# rev2.net
KiCad netlist of a schematic drawn in EAGLE
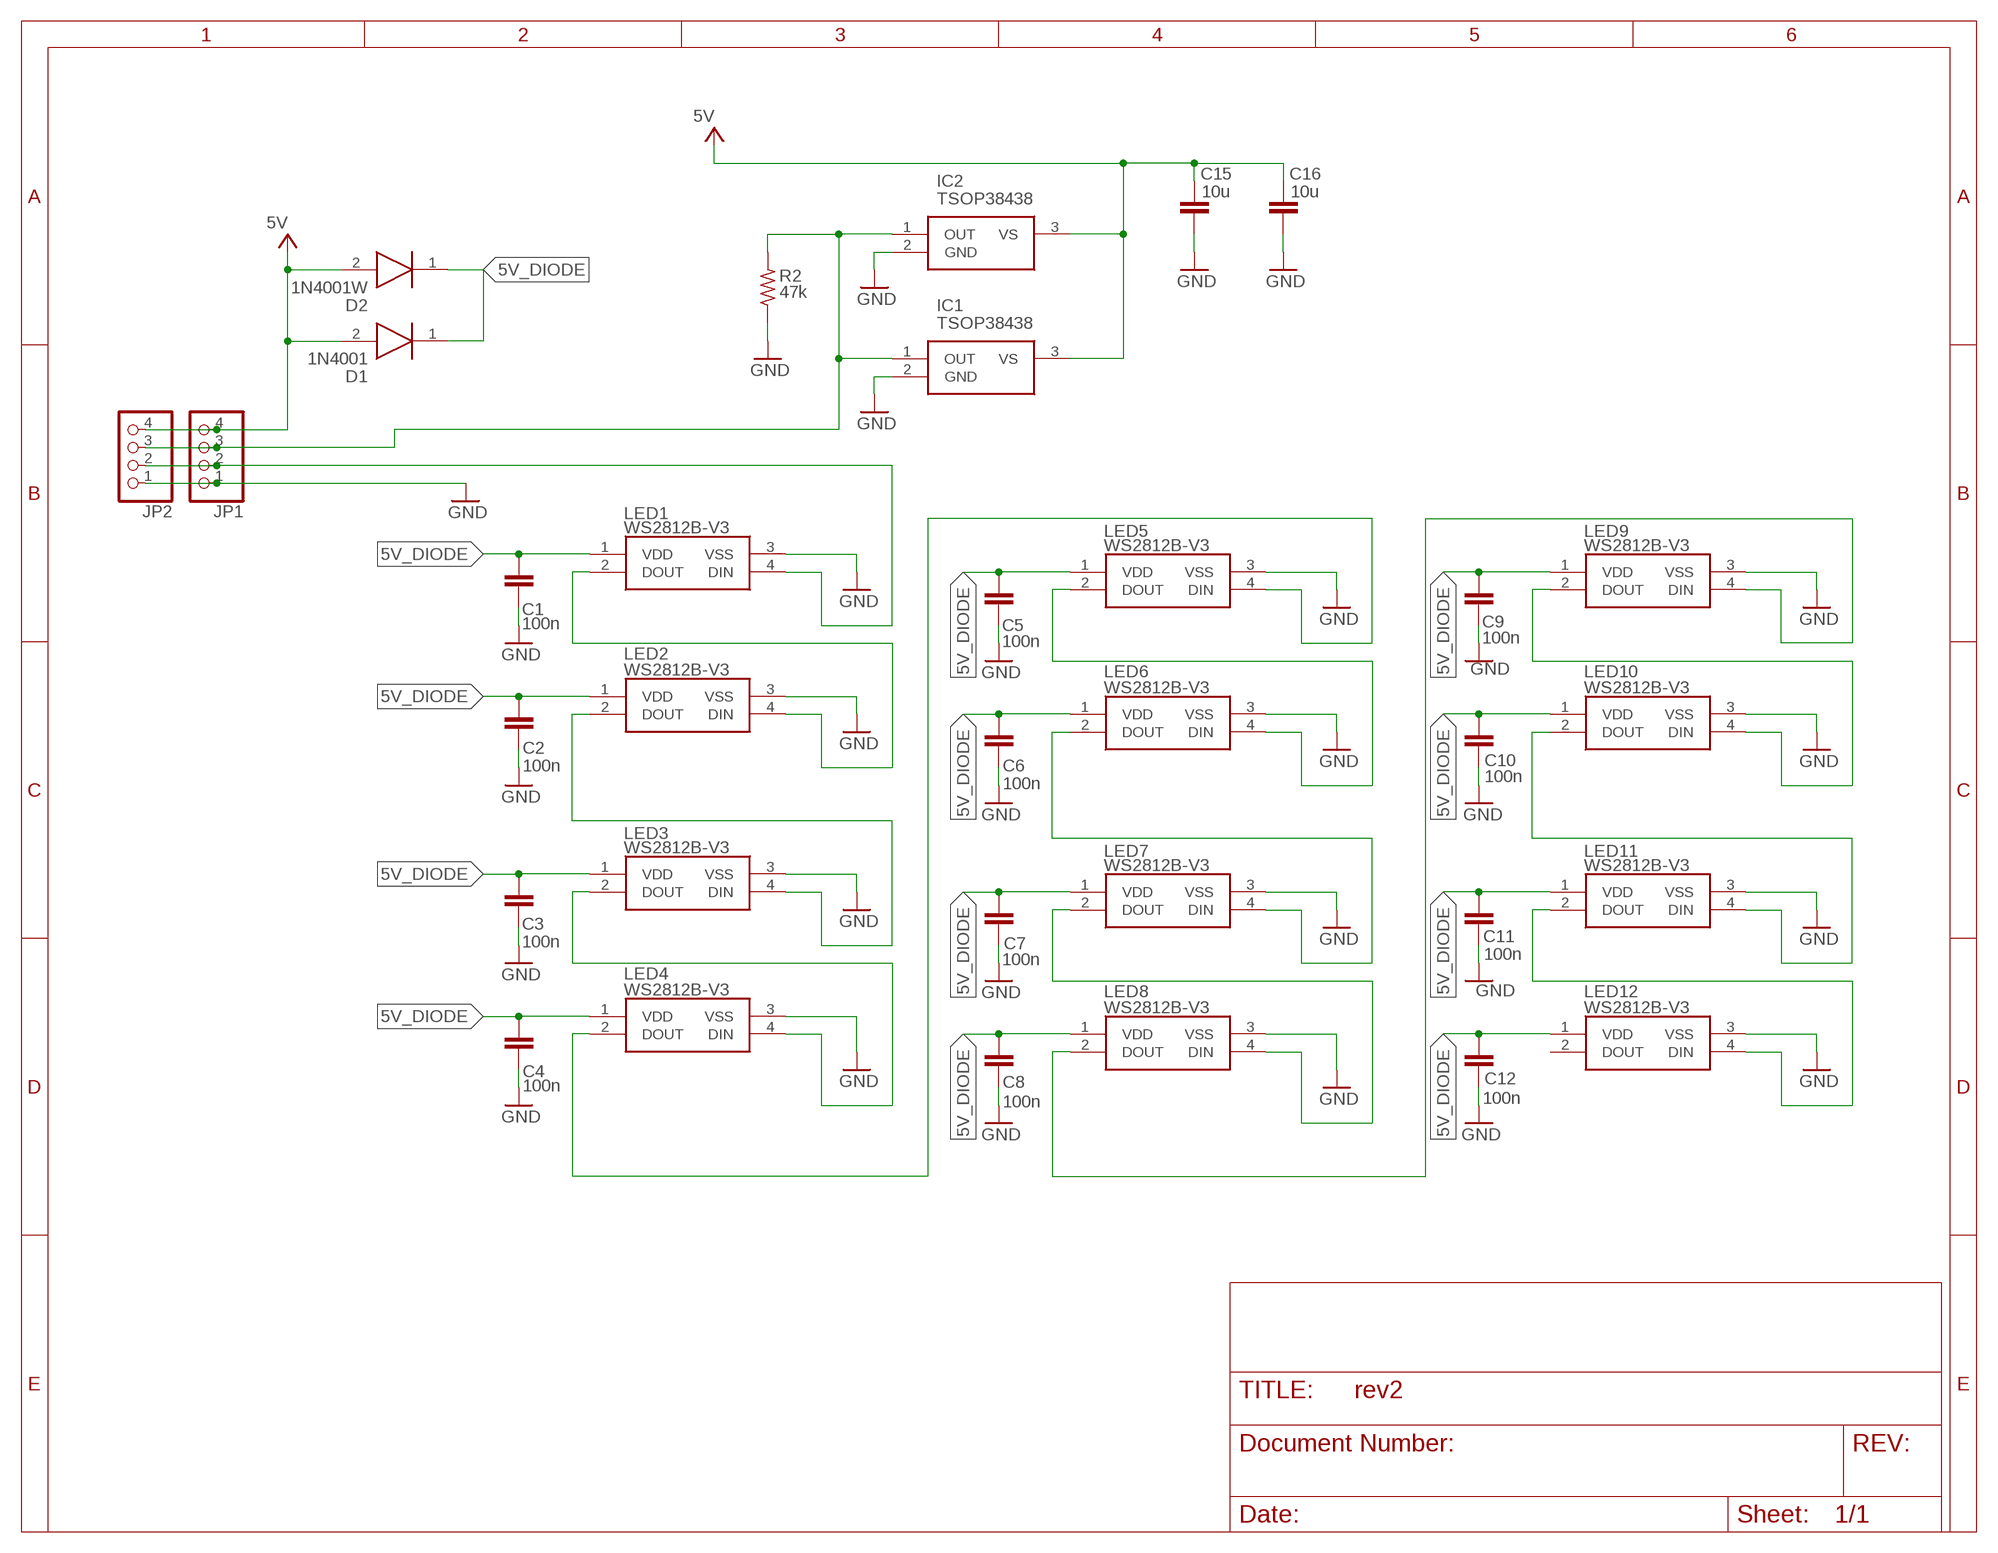
[diagram p0: schematic, sheet 1]

(export (version "E")
  (design (tool "Eeschema 10.0.6"))
  (components
    (comp (ref "C1")
      (value "100n")
      (footprint "eagle-import:C0805")
      (libsource (lib "eagle-import") (part "CAP_SMD0805"))
    )
    (comp (ref "C2")
      (value "100n")
      (footprint "eagle-import:C0805")
      (libsource (lib "eagle-import") (part "CAP_SMD0805"))
    )
    (comp (ref "C3")
      (value "100n")
      (footprint "eagle-import:C0805")
      (libsource (lib "eagle-import") (part "CAP_SMD0805"))
    )
    (comp (ref "C4")
      (value "100n")
      (footprint "eagle-import:C0805")
      (libsource (lib "eagle-import") (part "CAP_SMD0805"))
    )
    (comp (ref "C5")
      (value "100n")
      (footprint "eagle-import:C0805")
      (libsource (lib "eagle-import") (part "CAP_SMD0805"))
    )
    (comp (ref "C6")
      (value "100n")
      (footprint "eagle-import:C0805")
      (libsource (lib "eagle-import") (part "CAP_SMD0805"))
    )
    (comp (ref "C7")
      (value "100n")
      (footprint "eagle-import:C0805")
      (libsource (lib "eagle-import") (part "CAP_SMD0805"))
    )
    (comp (ref "C8")
      (value "100n")
      (footprint "eagle-import:C0805")
      (libsource (lib "eagle-import") (part "CAP_SMD0805"))
    )
    (comp (ref "C9")
      (value "100n")
      (footprint "eagle-import:C0805")
      (libsource (lib "eagle-import") (part "CAP_SMD0805"))
    )
    (comp (ref "C10")
      (value "100n")
      (footprint "eagle-import:C0805")
      (libsource (lib "eagle-import") (part "CAP_SMD0805"))
    )
    (comp (ref "C11")
      (value "100n")
      (footprint "eagle-import:C0805")
      (libsource (lib "eagle-import") (part "CAP_SMD0805"))
    )
    (comp (ref "C12")
      (value "100n")
      (footprint "eagle-import:C0805")
      (libsource (lib "eagle-import") (part "CAP_SMD0805"))
    )
    (comp (ref "C15")
      (value "10u")
      (footprint "eagle-import:C0805")
      (libsource (lib "eagle-import") (part "CAP_SMD0805"))
    )
    (comp (ref "C16")
      (value "10u")
      (footprint "eagle-import:C0805")
      (libsource (lib "eagle-import") (part "CAP_SMD0805"))
    )
    (comp (ref "D1")
      (value "1N4001")
      (footprint "eagle-import:DIOAD1405W86L465D235")
      (fields (field (name "RS_PART_NUMBER") "0261148A"))
      (libsource (lib "eagle-import") (part "1N4001"))
    )
    (comp (ref "D2")
      (value "1N4001W")
      (footprint "eagle-import:1N4001W")
      (libsource (lib "eagle-import") (part "1N4001W"))
    )
    (comp (ref "IC1")
      (value "TSOP38438")
      (footprint "eagle-import:TSOP38238")
      (fields (field (name "MOUSER_PART_NUMBER") "78-TSOP38438") (field (name "RS_PART_NUMBER") "7085092P"))
      (libsource (lib "eagle-import") (part "TSOP38438"))
    )
    (comp (ref "IC2")
      (value "TSOP38438")
      (footprint "eagle-import:TSOP38238")
      (fields (field (name "MOUSER_PART_NUMBER") "78-TSOP38438") (field (name "RS_PART_NUMBER") "7085092P"))
      (libsource (lib "eagle-import") (part "TSOP38438"))
    )
    (comp (ref "JP1")
      (value "PINHD-1X4")
      (footprint "eagle-import:1X04")
      (libsource (lib "eagle-import") (part "PINHD-1X4"))
    )
    (comp (ref "JP2")
      (value "PINHD-1X4")
      (footprint "eagle-import:1X04")
      (libsource (lib "eagle-import") (part "PINHD-1X4"))
    )
    (comp (ref "LED1")
      (value "WS2812B-V3")
      (footprint "eagle-import:WS2812BV3")
      (libsource (lib "eagle-import") (part "WS2812B-V3"))
    )
    (comp (ref "LED2")
      (value "WS2812B-V3")
      (footprint "eagle-import:WS2812BV3")
      (libsource (lib "eagle-import") (part "WS2812B-V3"))
    )
    (comp (ref "LED3")
      (value "WS2812B-V3")
      (footprint "eagle-import:WS2812BV3")
      (libsource (lib "eagle-import") (part "WS2812B-V3"))
    )
    (comp (ref "LED4")
      (value "WS2812B-V3")
      (footprint "eagle-import:WS2812BV3")
      (libsource (lib "eagle-import") (part "WS2812B-V3"))
    )
    (comp (ref "LED5")
      (value "WS2812B-V3")
      (footprint "eagle-import:WS2812BV3")
      (libsource (lib "eagle-import") (part "WS2812B-V3"))
    )
    (comp (ref "LED6")
      (value "WS2812B-V3")
      (footprint "eagle-import:WS2812BV3")
      (libsource (lib "eagle-import") (part "WS2812B-V3"))
    )
    (comp (ref "LED7")
      (value "WS2812B-V3")
      (footprint "eagle-import:WS2812BV3")
      (libsource (lib "eagle-import") (part "WS2812B-V3"))
    )
    (comp (ref "LED8")
      (value "WS2812B-V3")
      (footprint "eagle-import:WS2812BV3")
      (libsource (lib "eagle-import") (part "WS2812B-V3"))
    )
    (comp (ref "LED9")
      (value "WS2812B-V3")
      (footprint "eagle-import:WS2812BV3")
      (libsource (lib "eagle-import") (part "WS2812B-V3"))
    )
    (comp (ref "LED10")
      (value "WS2812B-V3")
      (footprint "eagle-import:WS2812BV3")
      (libsource (lib "eagle-import") (part "WS2812B-V3"))
    )
    (comp (ref "LED11")
      (value "WS2812B-V3")
      (footprint "eagle-import:WS2812BV3")
      (libsource (lib "eagle-import") (part "WS2812B-V3"))
    )
    (comp (ref "LED12")
      (value "WS2812B-V3")
      (footprint "eagle-import:WS2812BV3")
      (libsource (lib "eagle-import") (part "WS2812B-V3"))
    )
    (comp (ref "R2")
      (value "47k")
      (footprint "eagle-import:R0805")
      (libsource (lib "eagle-import") (part "RES_SMD0805"))
    )
  )
  (nets
    (net (code "1") (name "5V") (class "Default")
      (node (ref "C15") (pin "2") (pinfunction "2_2") (pintype "passive"))
      (node (ref "C16") (pin "2") (pinfunction "2_2") (pintype "passive"))
      (node (ref "D1") (pin "2") (pinfunction "A_2") (pintype "bidirectional"))
      (node (ref "D2") (pin "2") (pinfunction "A_2") (pintype "bidirectional"))
      (node (ref "IC1") (pin "3") (pinfunction "VS_3") (pintype "bidirectional"))
      (node (ref "IC2") (pin "3") (pinfunction "VS_3") (pintype "bidirectional"))
      (node (ref "JP1") (pin "4") (pinfunction "4_4") (pintype "passive"))
      (node (ref "JP2") (pin "4") (pinfunction "4_4") (pintype "passive"))
    )
    (net (code "2") (name "5V_DIODE") (class "Default")
      (node (ref "C1") (pin "2") (pinfunction "2_2") (pintype "passive"))
      (node (ref "C10") (pin "1") (pinfunction "1_1") (pintype "passive"))
      (node (ref "C11") (pin "2") (pinfunction "2_2") (pintype "passive"))
      (node (ref "C12") (pin "1") (pinfunction "1_1") (pintype "passive"))
      (node (ref "C2") (pin "1") (pinfunction "1_1") (pintype "passive"))
      (node (ref "C3") (pin "2") (pinfunction "2_2") (pintype "passive"))
      (node (ref "C4") (pin "1") (pinfunction "1_1") (pintype "passive"))
      (node (ref "C5") (pin "2") (pinfunction "2_2") (pintype "passive"))
      (node (ref "C6") (pin "1") (pinfunction "1_1") (pintype "passive"))
      (node (ref "C7") (pin "2") (pinfunction "2_2") (pintype "passive"))
      (node (ref "C8") (pin "1") (pinfunction "1_1") (pintype "passive"))
      (node (ref "C9") (pin "2") (pinfunction "2_2") (pintype "passive"))
      (node (ref "D1") (pin "1") (pinfunction "K_1") (pintype "bidirectional"))
      (node (ref "D2") (pin "1") (pinfunction "K_1") (pintype "bidirectional"))
      (node (ref "LED1") (pin "1") (pinfunction "VDD_1") (pintype "bidirectional"))
      (node (ref "LED10") (pin "1") (pinfunction "VDD_1") (pintype "bidirectional"))
      (node (ref "LED11") (pin "1") (pinfunction "VDD_1") (pintype "bidirectional"))
      (node (ref "LED12") (pin "1") (pinfunction "VDD_1") (pintype "bidirectional"))
      (node (ref "LED2") (pin "1") (pinfunction "VDD_1") (pintype "bidirectional"))
      (node (ref "LED3") (pin "1") (pinfunction "VDD_1") (pintype "bidirectional"))
      (node (ref "LED4") (pin "1") (pinfunction "VDD_1") (pintype "bidirectional"))
      (node (ref "LED5") (pin "1") (pinfunction "VDD_1") (pintype "bidirectional"))
      (node (ref "LED6") (pin "1") (pinfunction "VDD_1") (pintype "bidirectional"))
      (node (ref "LED7") (pin "1") (pinfunction "VDD_1") (pintype "bidirectional"))
      (node (ref "LED8") (pin "1") (pinfunction "VDD_1") (pintype "bidirectional"))
      (node (ref "LED9") (pin "1") (pinfunction "VDD_1") (pintype "bidirectional"))
    )
    (net (code "3") (name "GND") (class "Default")
      (node (ref "C1") (pin "1") (pinfunction "1_1") (pintype "passive"))
      (node (ref "C10") (pin "2") (pinfunction "2_2") (pintype "passive"))
      (node (ref "C11") (pin "1") (pinfunction "1_1") (pintype "passive"))
      (node (ref "C12") (pin "2") (pinfunction "2_2") (pintype "passive"))
      (node (ref "C15") (pin "1") (pinfunction "1_1") (pintype "passive"))
      (node (ref "C16") (pin "1") (pinfunction "1_1") (pintype "passive"))
      (node (ref "C2") (pin "2") (pinfunction "2_2") (pintype "passive"))
      (node (ref "C3") (pin "1") (pinfunction "1_1") (pintype "passive"))
      (node (ref "C4") (pin "2") (pinfunction "2_2") (pintype "passive"))
      (node (ref "C5") (pin "1") (pinfunction "1_1") (pintype "passive"))
      (node (ref "C6") (pin "2") (pinfunction "2_2") (pintype "passive"))
      (node (ref "C7") (pin "1") (pinfunction "1_1") (pintype "passive"))
      (node (ref "C8") (pin "2") (pinfunction "2_2") (pintype "passive"))
      (node (ref "C9") (pin "1") (pinfunction "1_1") (pintype "passive"))
      (node (ref "IC1") (pin "2") (pinfunction "GND_2") (pintype "bidirectional"))
      (node (ref "IC2") (pin "2") (pinfunction "GND_2") (pintype "bidirectional"))
      (node (ref "JP1") (pin "1") (pinfunction "1_1") (pintype "passive"))
      (node (ref "JP2") (pin "1") (pinfunction "1_1") (pintype "passive"))
      (node (ref "LED1") (pin "3") (pinfunction "VSS_3") (pintype "bidirectional"))
      (node (ref "LED10") (pin "3") (pinfunction "VSS_3") (pintype "bidirectional"))
      (node (ref "LED11") (pin "3") (pinfunction "VSS_3") (pintype "bidirectional"))
      (node (ref "LED12") (pin "3") (pinfunction "VSS_3") (pintype "bidirectional"))
      (node (ref "LED2") (pin "3") (pinfunction "VSS_3") (pintype "bidirectional"))
      (node (ref "LED3") (pin "3") (pinfunction "VSS_3") (pintype "bidirectional"))
      (node (ref "LED4") (pin "3") (pinfunction "VSS_3") (pintype "bidirectional"))
      (node (ref "LED5") (pin "3") (pinfunction "VSS_3") (pintype "bidirectional"))
      (node (ref "LED6") (pin "3") (pinfunction "VSS_3") (pintype "bidirectional"))
      (node (ref "LED7") (pin "3") (pinfunction "VSS_3") (pintype "bidirectional"))
      (node (ref "LED8") (pin "3") (pinfunction "VSS_3") (pintype "bidirectional"))
      (node (ref "LED9") (pin "3") (pinfunction "VSS_3") (pintype "bidirectional"))
      (node (ref "R2") (pin "1") (pinfunction "1_1") (pintype "passive"))
    )
    (net (code "4") (name "Net-(IC1-OUT)") (class "Default")
      (node (ref "IC1") (pin "1") (pinfunction "OUT_1") (pintype "bidirectional"))
      (node (ref "IC2") (pin "1") (pinfunction "OUT_1") (pintype "bidirectional"))
      (node (ref "JP1") (pin "3") (pinfunction "3_3") (pintype "passive"))
      (node (ref "JP2") (pin "3") (pinfunction "3_3") (pintype "passive"))
      (node (ref "R2") (pin "2") (pinfunction "2_2") (pintype "passive"))
    )
    (net (code "5") (name "Net-(LED1-DIN)") (class "Default")
      (node (ref "JP1") (pin "2") (pinfunction "2_2") (pintype "passive"))
      (node (ref "JP2") (pin "2") (pinfunction "2_2") (pintype "passive"))
      (node (ref "LED1") (pin "4") (pinfunction "DIN_4") (pintype "bidirectional"))
    )
    (net (code "6") (name "Net-(LED1-DOUT)") (class "Default")
      (node (ref "LED1") (pin "2") (pinfunction "DOUT_2") (pintype "bidirectional"))
      (node (ref "LED2") (pin "4") (pinfunction "DIN_4") (pintype "bidirectional"))
    )
    (net (code "7") (name "Net-(LED2-DOUT)") (class "Default")
      (node (ref "LED2") (pin "2") (pinfunction "DOUT_2") (pintype "bidirectional"))
      (node (ref "LED3") (pin "4") (pinfunction "DIN_4") (pintype "bidirectional"))
    )
    (net (code "8") (name "Net-(LED3-DOUT)") (class "Default")
      (node (ref "LED3") (pin "2") (pinfunction "DOUT_2") (pintype "bidirectional"))
      (node (ref "LED4") (pin "4") (pinfunction "DIN_4") (pintype "bidirectional"))
    )
    (net (code "9") (name "Net-(LED4-DOUT)") (class "Default")
      (node (ref "LED4") (pin "2") (pinfunction "DOUT_2") (pintype "bidirectional"))
      (node (ref "LED5") (pin "4") (pinfunction "DIN_4") (pintype "bidirectional"))
    )
    (net (code "10") (name "Net-(LED5-DOUT)") (class "Default")
      (node (ref "LED5") (pin "2") (pinfunction "DOUT_2") (pintype "bidirectional"))
      (node (ref "LED6") (pin "4") (pinfunction "DIN_4") (pintype "bidirectional"))
    )
    (net (code "11") (name "Net-(LED6-DOUT)") (class "Default")
      (node (ref "LED6") (pin "2") (pinfunction "DOUT_2") (pintype "bidirectional"))
      (node (ref "LED7") (pin "4") (pinfunction "DIN_4") (pintype "bidirectional"))
    )
    (net (code "12") (name "Net-(LED7-DOUT)") (class "Default")
      (node (ref "LED7") (pin "2") (pinfunction "DOUT_2") (pintype "bidirectional"))
      (node (ref "LED8") (pin "4") (pinfunction "DIN_4") (pintype "bidirectional"))
    )
    (net (code "13") (name "Net-(LED8-DOUT)") (class "Default")
      (node (ref "LED8") (pin "2") (pinfunction "DOUT_2") (pintype "bidirectional"))
      (node (ref "LED9") (pin "4") (pinfunction "DIN_4") (pintype "bidirectional"))
    )
    (net (code "14") (name "Net-(LED10-DIN)") (class "Default")
      (node (ref "LED10") (pin "4") (pinfunction "DIN_4") (pintype "bidirectional"))
      (node (ref "LED9") (pin "2") (pinfunction "DOUT_2") (pintype "bidirectional"))
    )
    (net (code "15") (name "Net-(LED10-DOUT)") (class "Default")
      (node (ref "LED10") (pin "2") (pinfunction "DOUT_2") (pintype "bidirectional"))
      (node (ref "LED11") (pin "4") (pinfunction "DIN_4") (pintype "bidirectional"))
    )
    (net (code "16") (name "Net-(LED11-DOUT)") (class "Default")
      (node (ref "LED11") (pin "2") (pinfunction "DOUT_2") (pintype "bidirectional"))
      (node (ref "LED12") (pin "4") (pinfunction "DIN_4") (pintype "bidirectional"))
    )
    (net (code "17") (name "unconnected-(LED12-DOUT-Pad2)") (class "Default")
      (node (ref "LED12") (pin "2") (pinfunction "DOUT_2") (pintype "bidirectional"))
    )
  )
)
